# Sheet1.net
KiCad netlist of a schematic drawn in Altium Designer
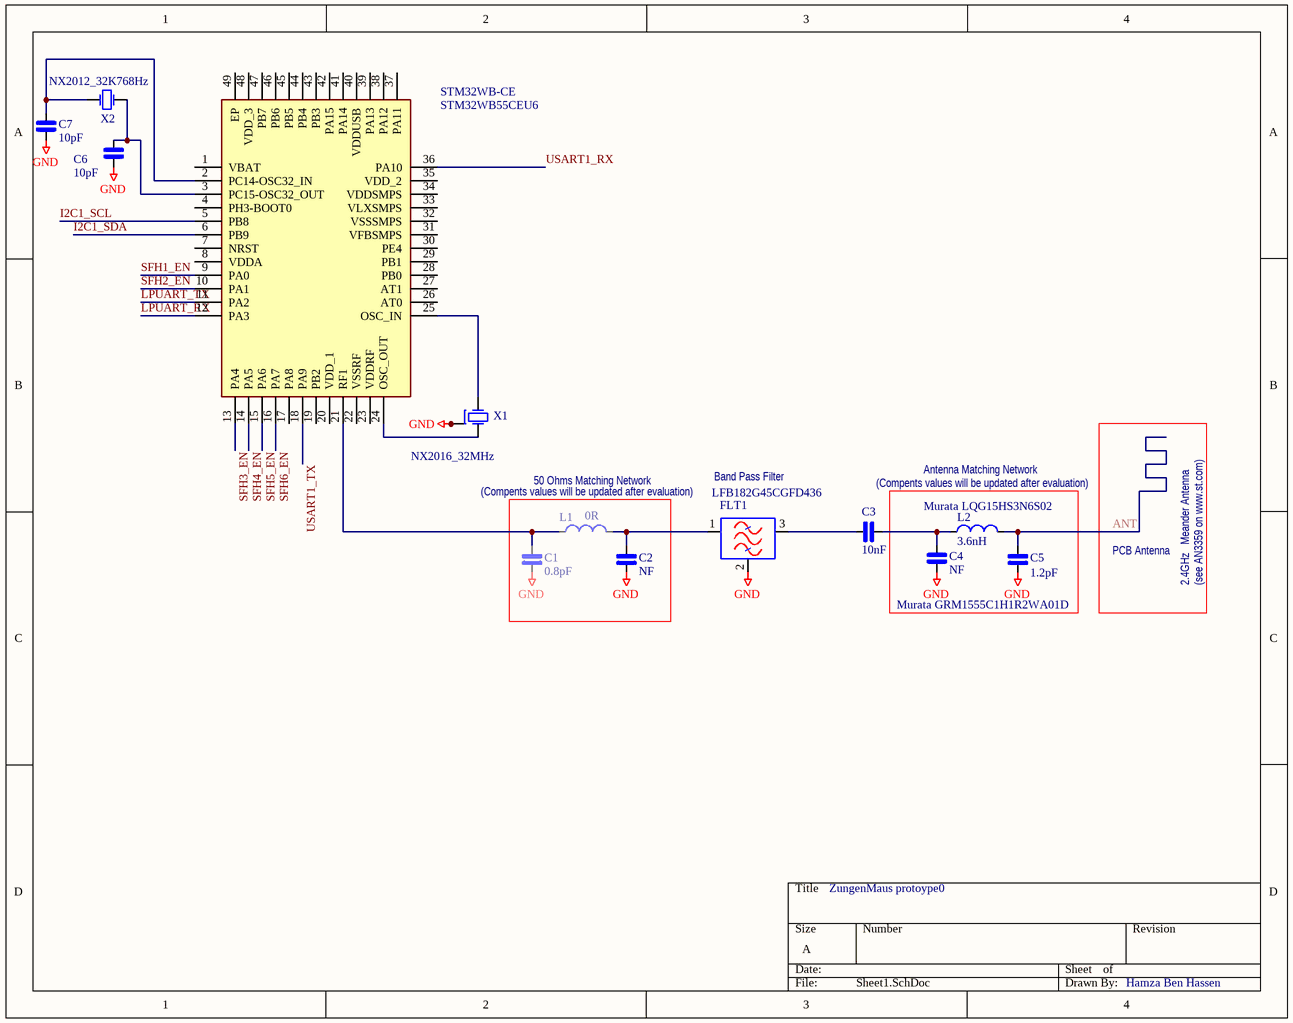
[diagram p0: Sheet1.SchDoc]

(export (version "E")
  (design (tool "Eeschema 10.0.6"))
  (components
    (comp (ref "C1")
      (value "0.8pF")
      (footprint "0402_CAP_NPOL")
      (description "Capacitor_not polarized")
      (libsource (lib "Passive") (part "CAP_NPOL"))
    )
    (comp (ref "C2")
      (value "NF")
      (footprint "0402_CAP_NPOL")
      (description "Capacitor_not polarized")
      (libsource (lib "Passive") (part "CAP_NPOL"))
    )
    (comp (ref "C3")
      (value "10nF")
      (footprint "0402_CAP_NPOL")
      (description "Capacitor_not polarized")
      (libsource (lib "Passive") (part "CAP_NPOL"))
    )
    (comp (ref "C4")
      (value "NF")
      (footprint "0402_CAP_NPOL")
      (description "Capacitor_not polarized")
      (libsource (lib "Passive") (part "CAP_NPOL"))
    )
    (comp (ref "C5")
      (value "1.2pF")
      (footprint "0402_CAP_NPOL")
      (description "Capacitor_not polarized")
      (fields (field (name "REF") "Murata GRM1555C1H1R2WA01D"))
      (libsource (lib "ST_Lib3D") (part "CAP_NPOL"))
    )
    (comp (ref "C6")
      (value "10pF")
      (footprint "0402_CAP_NPOL")
      (description "Capacitor_not polarized")
      (libsource (lib "ST_Lib3D") (part "CAP_NPOL"))
    )
    (comp (ref "C7")
      (value "10pF")
      (footprint "0402_CAP_NPOL")
      (description "Capacitor_not polarized")
      (libsource (lib "ST_Lib3D") (part "CAP_NPOL"))
    )
    (comp (ref "FLT1")
      (value "LFB182G45CGFD436")
      (footprint "LFB182G45CGFD436")
      (description "Band Pass Filter Murata LFB182G45CGFD436")
      (libsource (lib "Passive") (part "LFB182G45CGFD436"))
    )
    (comp (ref "L1")
      (value "0R")
      (footprint "0402_COIL")
      (libsource (lib "Passive") (part "INDUCTOR_SMD_STDL"))
    )
    (comp (ref "L2")
      (value "3.6nH")
      (footprint "0402_COIL")
      (fields (field (name "REF") "Murata LQG15HS3N6S02"))
      (libsource (lib "Passive") (part "INDUCTOR_SMD_STDL"))
    )
    (comp (ref "STM32WB-CE")
      (value "STM32WB55CEU6")
      (footprint "SamacSys:QFN50P700X700X65-49N-D")
      (description "Integrated Circuit")
      (fields (field (name "MOUSER PART NUMBER") "511-STM32WB55CEU6"))
      (libsource (lib "*") (part "STM32WB55CEU6"))
    )
    (comp (ref "X1")
      (value "NX2016_32MHz")
      (footprint "NX2016_4P")
      (description "Crystal NDK 2.0x1.6mm  32 MHz")
      (fields (field (name "MANUFACTURER") "NDK"))
      (libsource (lib "Xtal") (part "NX2016_32M"))
    )
    (comp (ref "X2")
      (value "NX2012_32K768Hz")
      (footprint "NX2012_2P")
      (description "Crystal NDK 2.0x1.2mm  32.768 KHz")
      (fields (field (name "MANUFACTURER") "NDK"))
      (libsource (lib "Xtal") (part "NX2012_32K768"))
    )
  )
  (nets
    (net (code "1") (name "/ANT") (class "Default")
      (node (ref "C5") (pin "2") (pinfunction "2_2") (pintype "passive"))
      (node (ref "L2") (pin "2") (pinfunction "2_2") (pintype "passive"))
    )
    (net (code "2") (name "/I2C1_SCL") (class "Default")
      (node (ref "STM32WB-CE") (pin "5") (pinfunction "PB8_5") (pintype "passive"))
    )
    (net (code "3") (name "/I2C1_SDA") (class "Default")
      (node (ref "STM32WB-CE") (pin "6") (pinfunction "PB9_6") (pintype "passive"))
    )
    (net (code "4") (name "/LPUART_RX") (class "Default")
      (node (ref "STM32WB-CE") (pin "12") (pinfunction "PA3_12") (pintype "passive"))
    )
    (net (code "5") (name "/LPUART_TX") (class "Default")
      (node (ref "STM32WB-CE") (pin "11") (pinfunction "PA2_11") (pintype "passive"))
    )
    (net (code "6") (name "/SFH1_EN") (class "Default")
      (node (ref "STM32WB-CE") (pin "9") (pinfunction "PA0_9") (pintype "passive"))
    )
    (net (code "7") (name "/SFH2_EN") (class "Default")
      (node (ref "STM32WB-CE") (pin "10") (pinfunction "PA1_10") (pintype "passive"))
    )
    (net (code "8") (name "/SFH3_EN") (class "Default")
      (node (ref "STM32WB-CE") (pin "13") (pinfunction "PA4_13") (pintype "passive"))
    )
    (net (code "9") (name "/SFH4_EN") (class "Default")
      (node (ref "STM32WB-CE") (pin "14") (pinfunction "PA5_14") (pintype "passive"))
    )
    (net (code "10") (name "/SFH5_EN") (class "Default")
      (node (ref "STM32WB-CE") (pin "15") (pinfunction "PA6_15") (pintype "passive"))
    )
    (net (code "11") (name "/SFH6_EN") (class "Default")
      (node (ref "STM32WB-CE") (pin "16") (pinfunction "PA7_16") (pintype "passive"))
    )
    (net (code "12") (name "/USART1_RX") (class "Default")
      (node (ref "STM32WB-CE") (pin "36") (pinfunction "PA10_36") (pintype "passive"))
    )
    (net (code "13") (name "/USART1_TX") (class "Default")
      (node (ref "STM32WB-CE") (pin "18") (pinfunction "PA9_18") (pintype "passive"))
    )
    (net (code "14") (name "GND") (class "Default")
      (node (ref "C1") (pin "1") (pinfunction "1_1") (pintype "passive"))
      (node (ref "C2") (pin "1") (pinfunction "1_1") (pintype "passive"))
      (node (ref "C4") (pin "2") (pinfunction "2_2") (pintype "passive"))
      (node (ref "C5") (pin "1") (pinfunction "1_1") (pintype "passive"))
      (node (ref "C6") (pin "2") (pinfunction "2_2") (pintype "passive"))
      (node (ref "C7") (pin "2") (pinfunction "2_2") (pintype "passive"))
      (node (ref "FLT1") (pin "2") (pinfunction "GND_2") (pintype "passive"))
      (node (ref "X1") (pin "2") (pinfunction "2_2") (pintype "passive"))
      (node (ref "X1") (pin "4") (pinfunction "4_4") (pintype "passive"))
    )
    (net (code "15") (name "Net-(C2-Pad2)") (class "Default")
      (node (ref "C2") (pin "2") (pinfunction "2_2") (pintype "passive"))
      (node (ref "FLT1") (pin "1") (pinfunction "I/O_1") (pintype "passive"))
      (node (ref "L1") (pin "2") (pinfunction "2_2") (pintype "passive"))
    )
    (net (code "16") (name "Net-(C3-Pad1)") (class "Default")
      (node (ref "C3") (pin "1") (pinfunction "1_1") (pintype "passive"))
      (node (ref "FLT1") (pin "3") (pinfunction "I/O_3") (pintype "passive"))
    )
    (net (code "17") (name "Net-(C3-Pad2)") (class "Default")
      (node (ref "C3") (pin "2") (pinfunction "2_2") (pintype "passive"))
      (node (ref "C4") (pin "1") (pinfunction "1_1") (pintype "passive"))
      (node (ref "L2") (pin "1") (pinfunction "1_1") (pintype "passive"))
    )
    (net (code "18") (name "Net-(STM32WB-CE-OSC_IN)") (class "Default")
      (node (ref "STM32WB-CE") (pin "25") (pinfunction "OSC_IN_25") (pintype "passive"))
      (node (ref "X1") (pin "1") (pinfunction "OSC1_1") (pintype "passive"))
    )
    (net (code "19") (name "Net-(STM32WB-CE-OSC_OUT)") (class "Default")
      (node (ref "STM32WB-CE") (pin "24") (pinfunction "OSC_OUT_24") (pintype "passive"))
      (node (ref "X1") (pin "3") (pinfunction "OSC2_3") (pintype "passive"))
    )
    (net (code "20") (name "Net-(STM32WB-CE-PC14-OSC32_IN)") (class "Default")
      (node (ref "C7") (pin "1") (pinfunction "1_1") (pintype "passive"))
      (node (ref "STM32WB-CE") (pin "2") (pinfunction "PC14-OSC32_IN_2") (pintype "passive"))
      (node (ref "X2") (pin "1") (pinfunction "OSC1_1") (pintype "passive"))
    )
    (net (code "21") (name "Net-(STM32WB-CE-PC15-OSC32_OUT)") (class "Default")
      (node (ref "C6") (pin "1") (pinfunction "1_1") (pintype "passive"))
      (node (ref "STM32WB-CE") (pin "3") (pinfunction "PC15-OSC32_OUT_3") (pintype "passive"))
      (node (ref "X2") (pin "2") (pinfunction "OSC2_2") (pintype "passive"))
    )
    (net (code "22") (name "Net-(STM32WB-CE-RF1)") (class "Default")
      (node (ref "C1") (pin "2") (pinfunction "2_2") (pintype "passive"))
      (node (ref "L1") (pin "1") (pinfunction "1_1") (pintype "passive"))
      (node (ref "STM32WB-CE") (pin "21") (pinfunction "RF1_21") (pintype "passive"))
    )
    (net (code "23") (name "unconnected-(STM32WB-CE-AT0-Pad26)") (class "Default")
      (node (ref "STM32WB-CE") (pin "26") (pinfunction "AT0_26") (pintype "passive"))
    )
    (net (code "24") (name "unconnected-(STM32WB-CE-AT1-Pad27)") (class "Default")
      (node (ref "STM32WB-CE") (pin "27") (pinfunction "AT1_27") (pintype "passive"))
    )
    (net (code "25") (name "unconnected-(STM32WB-CE-EP-Pad49)") (class "Default")
      (node (ref "STM32WB-CE") (pin "49") (pinfunction "EP_49") (pintype "passive"))
    )
    (net (code "26") (name "unconnected-(STM32WB-CE-NRST-Pad7)") (class "Default")
      (node (ref "STM32WB-CE") (pin "7") (pinfunction "NRST_7") (pintype "passive"))
    )
    (net (code "27") (name "unconnected-(STM32WB-CE-PA8-Pad17)") (class "Default")
      (node (ref "STM32WB-CE") (pin "17") (pinfunction "PA8_17") (pintype "power_in"))
    )
    (net (code "28") (name "unconnected-(STM32WB-CE-PA11-Pad37)") (class "Default")
      (node (ref "STM32WB-CE") (pin "37") (pinfunction "PA11_37") (pintype "passive"))
    )
    (net (code "29") (name "unconnected-(STM32WB-CE-PA12-Pad38)") (class "Default")
      (node (ref "STM32WB-CE") (pin "38") (pinfunction "PA12_38") (pintype "passive"))
    )
    (net (code "30") (name "unconnected-(STM32WB-CE-PA13-Pad39)") (class "Default")
      (node (ref "STM32WB-CE") (pin "39") (pinfunction "PA13_39") (pintype "passive"))
    )
    (net (code "31") (name "unconnected-(STM32WB-CE-PA14-Pad41)") (class "Default")
      (node (ref "STM32WB-CE") (pin "41") (pinfunction "PA14_41") (pintype "passive"))
    )
    (net (code "32") (name "unconnected-(STM32WB-CE-PA15-Pad42)") (class "Default")
      (node (ref "STM32WB-CE") (pin "42") (pinfunction "PA15_42") (pintype "passive"))
    )
    (net (code "33") (name "unconnected-(STM32WB-CE-PB0-Pad28)") (class "Default")
      (node (ref "STM32WB-CE") (pin "28") (pinfunction "PB0_28") (pintype "passive"))
    )
    (net (code "34") (name "unconnected-(STM32WB-CE-PB1-Pad29)") (class "Default")
      (node (ref "STM32WB-CE") (pin "29") (pinfunction "PB1_29") (pintype "passive"))
    )
    (net (code "35") (name "unconnected-(STM32WB-CE-PB2-Pad19)") (class "Default")
      (node (ref "STM32WB-CE") (pin "19") (pinfunction "PB2_19") (pintype "passive"))
    )
    (net (code "36") (name "unconnected-(STM32WB-CE-PB3-Pad43)") (class "Default")
      (node (ref "STM32WB-CE") (pin "43") (pinfunction "PB3_43") (pintype "passive"))
    )
    (net (code "37") (name "unconnected-(STM32WB-CE-PB4-Pad44)") (class "Default")
      (node (ref "STM32WB-CE") (pin "44") (pinfunction "PB4_44") (pintype "passive"))
    )
    (net (code "38") (name "unconnected-(STM32WB-CE-PB5-Pad45)") (class "Default")
      (node (ref "STM32WB-CE") (pin "45") (pinfunction "PB5_45") (pintype "passive"))
    )
    (net (code "39") (name "unconnected-(STM32WB-CE-PB6-Pad46)") (class "Default")
      (node (ref "STM32WB-CE") (pin "46") (pinfunction "PB6_46") (pintype "passive"))
    )
    (net (code "40") (name "unconnected-(STM32WB-CE-PB7-Pad47)") (class "Default")
      (node (ref "STM32WB-CE") (pin "47") (pinfunction "PB7_47") (pintype "passive"))
    )
    (net (code "41") (name "unconnected-(STM32WB-CE-PE4-Pad30)") (class "Default")
      (node (ref "STM32WB-CE") (pin "30") (pinfunction "PE4_30") (pintype "passive"))
    )
    (net (code "42") (name "unconnected-(STM32WB-CE-PH3-BOOT0-Pad4)") (class "Default")
      (node (ref "STM32WB-CE") (pin "4") (pinfunction "PH3-BOOT0_4") (pintype "passive"))
    )
    (net (code "43") (name "unconnected-(STM32WB-CE-VBAT-Pad1)") (class "Default")
      (node (ref "STM32WB-CE") (pin "1") (pinfunction "VBAT_1") (pintype "passive"))
    )
    (net (code "44") (name "unconnected-(STM32WB-CE-VDDA-Pad8)") (class "Default")
      (node (ref "STM32WB-CE") (pin "8") (pinfunction "VDDA_8") (pintype "passive"))
    )
    (net (code "45") (name "unconnected-(STM32WB-CE-VDDRF-Pad23)") (class "Default")
      (node (ref "STM32WB-CE") (pin "23") (pinfunction "VDDRF_23") (pintype "passive"))
    )
    (net (code "46") (name "unconnected-(STM32WB-CE-VDDSMPS-Pad34)") (class "Default")
      (node (ref "STM32WB-CE") (pin "34") (pinfunction "VDDSMPS_34") (pintype "passive"))
    )
    (net (code "47") (name "unconnected-(STM32WB-CE-VDDUSB-Pad40)") (class "Default")
      (node (ref "STM32WB-CE") (pin "40") (pinfunction "VDDUSB_40") (pintype "passive"))
    )
    (net (code "48") (name "unconnected-(STM32WB-CE-VDD_1-Pad20)") (class "Default")
      (node (ref "STM32WB-CE") (pin "20") (pinfunction "VDD_1_20") (pintype "passive"))
    )
    (net (code "49") (name "unconnected-(STM32WB-CE-VDD_2-Pad35)") (class "Default")
      (node (ref "STM32WB-CE") (pin "35") (pinfunction "VDD_2_35") (pintype "passive"))
    )
    (net (code "50") (name "unconnected-(STM32WB-CE-VDD_3-Pad48)") (class "Default")
      (node (ref "STM32WB-CE") (pin "48") (pinfunction "VDD_3_48") (pintype "passive"))
    )
    (net (code "51") (name "unconnected-(STM32WB-CE-VFBSMPS-Pad31)") (class "Default")
      (node (ref "STM32WB-CE") (pin "31") (pinfunction "VFBSMPS_31") (pintype "passive"))
    )
    (net (code "52") (name "unconnected-(STM32WB-CE-VLXSMPS-Pad33)") (class "Default")
      (node (ref "STM32WB-CE") (pin "33") (pinfunction "VLXSMPS_33") (pintype "passive"))
    )
    (net (code "53") (name "unconnected-(STM32WB-CE-VSSRF-Pad22)") (class "Default")
      (node (ref "STM32WB-CE") (pin "22") (pinfunction "VSSRF_22") (pintype "passive"))
    )
    (net (code "54") (name "unconnected-(STM32WB-CE-VSSSMPS-Pad32)") (class "Default")
      (node (ref "STM32WB-CE") (pin "32") (pinfunction "VSSSMPS_32") (pintype "passive"))
    )
  )
)
